# screw-front-single-a-1.net
KiCad netlist of a schematic drawn in EAGLE
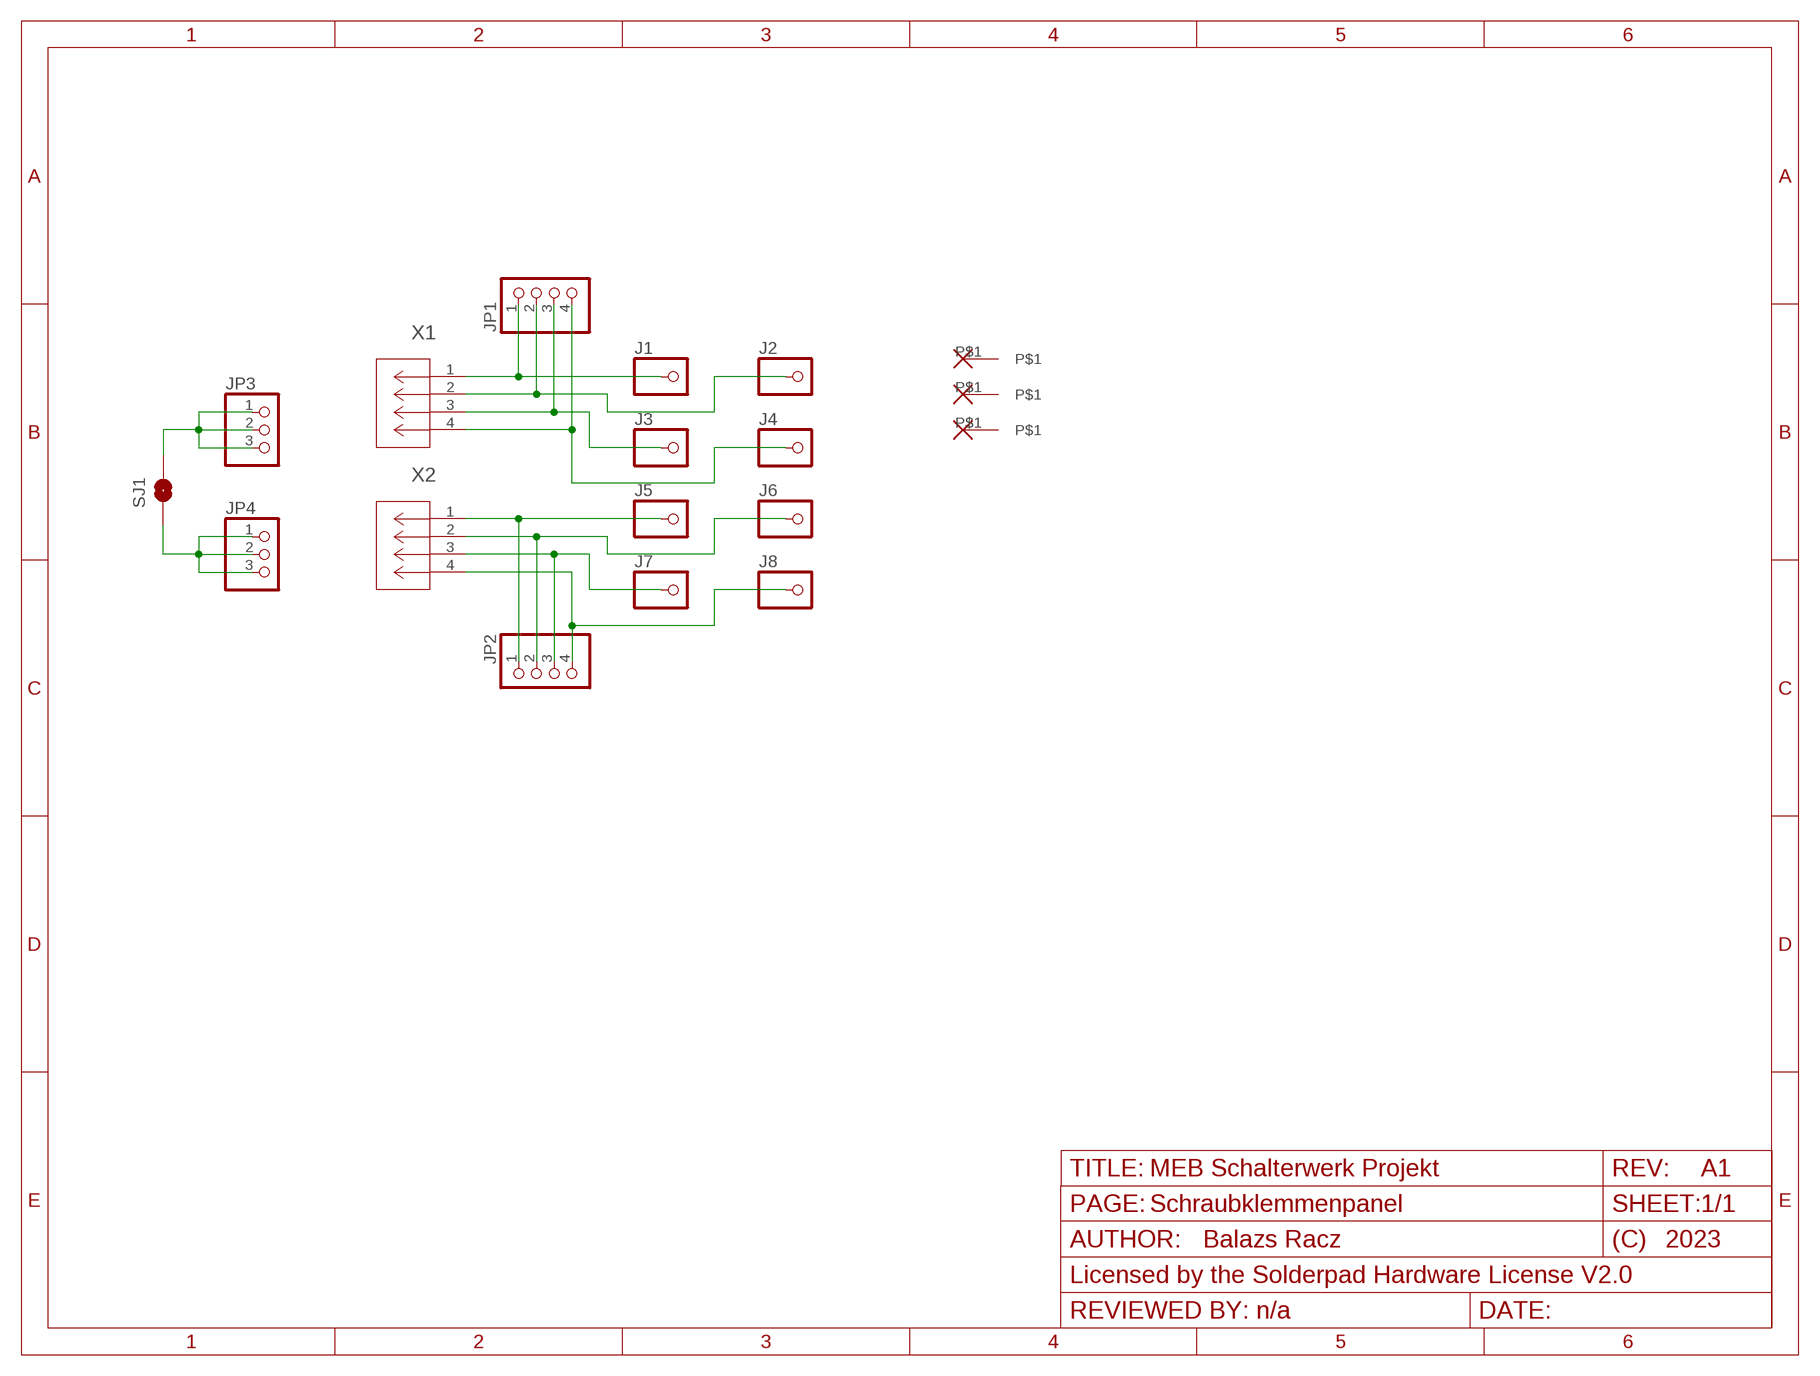
[diagram p0: schematic, sheet 1]

(export (version "E")
  (design (tool "Eeschema 10.0.6"))
  (components
    (comp (ref "H5")
      (value "ALIGN-HOLE")
      (footprint "eagle-import:ALIGNMENT-HOLE")
      (libsource (lib "eagle-import") (part "ALIGN-HOLE"))
    )
    (comp (ref "H6")
      (value "ALIGN-HOLE")
      (footprint "eagle-import:ALIGNMENT-HOLE")
      (libsource (lib "eagle-import") (part "ALIGN-HOLE"))
    )
    (comp (ref "H7")
      (value "ALIGN-HOLE")
      (footprint "eagle-import:ALIGNMENT-HOLE")
      (libsource (lib "eagle-import") (part "ALIGN-HOLE"))
    )
    (comp (ref "J1")
      (value "M4-SCREW-HOLE")
      (footprint "eagle-import:M4-SCREW-HOLE")
      (libsource (lib "eagle-import") (part "M4-SCREW-HOLE"))
    )
    (comp (ref "J2")
      (value "M4-SCREW-HOLE")
      (footprint "eagle-import:M4-SCREW-HOLE")
      (libsource (lib "eagle-import") (part "M4-SCREW-HOLE"))
    )
    (comp (ref "J3")
      (value "M4-SCREW-HOLE")
      (footprint "eagle-import:M4-SCREW-HOLE")
      (libsource (lib "eagle-import") (part "M4-SCREW-HOLE"))
    )
    (comp (ref "J4")
      (value "M4-SCREW-HOLE")
      (footprint "eagle-import:M4-SCREW-HOLE")
      (libsource (lib "eagle-import") (part "M4-SCREW-HOLE"))
    )
    (comp (ref "J5")
      (value "M4-SCREW-HOLE")
      (footprint "eagle-import:M4-SCREW-HOLE")
      (libsource (lib "eagle-import") (part "M4-SCREW-HOLE"))
    )
    (comp (ref "J6")
      (value "M4-SCREW-HOLE")
      (footprint "eagle-import:M4-SCREW-HOLE")
      (libsource (lib "eagle-import") (part "M4-SCREW-HOLE"))
    )
    (comp (ref "J7")
      (value "M4-SCREW-HOLE")
      (footprint "eagle-import:M4-SCREW-HOLE")
      (libsource (lib "eagle-import") (part "M4-SCREW-HOLE"))
    )
    (comp (ref "J8")
      (value "M4-SCREW-HOLE")
      (footprint "eagle-import:M4-SCREW-HOLE")
      (libsource (lib "eagle-import") (part "M4-SCREW-HOLE"))
    )
    (comp (ref "JP1")
      (value "PINHD-1X4")
      (footprint "eagle-import:1X04")
      (libsource (lib "eagle-import") (part "PINHD-1X4"))
    )
    (comp (ref "JP2")
      (value "PINHD-1X4")
      (footprint "eagle-import:1X04")
      (libsource (lib "eagle-import") (part "PINHD-1X4"))
    )
    (comp (ref "JP3")
      (value "PINHD-1X3")
      (footprint "eagle-import:1X03")
      (libsource (lib "eagle-import") (part "PINHD-1X3"))
    )
    (comp (ref "JP4")
      (value "PINHD-1X3")
      (footprint "eagle-import:1X03")
      (libsource (lib "eagle-import") (part "PINHD-1X3"))
    )
    (comp (ref "SJ1")
      (value "SJRND2")
      (footprint "eagle-import:SJ_RND2")
      (libsource (lib "eagle-import") (part "SJRND2"))
    )
    (comp (ref "X1")
      (value "PHNX_4P_350CONN_1984989_PXC")
      (footprint "eagle-import:PHNX_4P_350")
      (fields
        (field (name "MANUFACTURER_PART_NUMBER") "1984989")
        (field (name "COPYRIGHT") "Copyright (C) 2023 Ultra Librarian. All rights reserved.")
      )
      (libsource (lib "eagle-import") (part "PHNX_4P_350CONN_1984989_PXC"))
    )
    (comp (ref "X2")
      (value "PHNX_4P_350CONN_1984989_PXC")
      (footprint "eagle-import:PHNX_4P_350")
      (fields
        (field (name "MANUFACTURER_PART_NUMBER") "1984989")
        (field (name "COPYRIGHT") "Copyright (C) 2023 Ultra Librarian. All rights reserved.")
      )
      (libsource (lib "eagle-import") (part "PHNX_4P_350CONN_1984989_PXC"))
    )
  )
  (nets
    (net (code "1") (name "Net-(J1-1)") (class "Default")
      (node (ref "J1") (pin "P$1") (pinfunction "1_P$1") (pintype "passive"))
      (node (ref "JP1") (pin "1") (pinfunction "1_1") (pintype "passive"))
      (node (ref "X1") (pin "1") (pinfunction "1_1") (pintype "passive"))
    )
    (net (code "2") (name "Net-(J2-1)") (class "Default")
      (node (ref "J2") (pin "P$1") (pinfunction "1_P$1") (pintype "passive"))
      (node (ref "JP1") (pin "2") (pinfunction "2_2") (pintype "passive"))
      (node (ref "X1") (pin "2") (pinfunction "2_2") (pintype "passive"))
    )
    (net (code "3") (name "Net-(J3-1)") (class "Default")
      (node (ref "J3") (pin "P$1") (pinfunction "1_P$1") (pintype "passive"))
      (node (ref "JP1") (pin "3") (pinfunction "3_3") (pintype "passive"))
      (node (ref "X1") (pin "3") (pinfunction "3_3") (pintype "passive"))
    )
    (net (code "4") (name "Net-(J4-1)") (class "Default")
      (node (ref "J4") (pin "P$1") (pinfunction "1_P$1") (pintype "passive"))
      (node (ref "JP1") (pin "4") (pinfunction "4_4") (pintype "passive"))
      (node (ref "X1") (pin "4") (pinfunction "4_4") (pintype "passive"))
    )
    (net (code "5") (name "Net-(J5-1)") (class "Default")
      (node (ref "J5") (pin "P$1") (pinfunction "1_P$1") (pintype "passive"))
      (node (ref "JP2") (pin "1") (pinfunction "1_1") (pintype "passive"))
      (node (ref "X2") (pin "1") (pinfunction "1_1") (pintype "passive"))
    )
    (net (code "6") (name "Net-(J6-1)") (class "Default")
      (node (ref "J6") (pin "P$1") (pinfunction "1_P$1") (pintype "passive"))
      (node (ref "JP2") (pin "2") (pinfunction "2_2") (pintype "passive"))
      (node (ref "X2") (pin "2") (pinfunction "2_2") (pintype "passive"))
    )
    (net (code "7") (name "Net-(J7-1)") (class "Default")
      (node (ref "J7") (pin "P$1") (pinfunction "1_P$1") (pintype "passive"))
      (node (ref "JP2") (pin "3") (pinfunction "3_3") (pintype "passive"))
      (node (ref "X2") (pin "3") (pinfunction "3_3") (pintype "passive"))
    )
    (net (code "8") (name "Net-(J8-1)") (class "Default")
      (node (ref "J8") (pin "P$1") (pinfunction "1_P$1") (pintype "passive"))
      (node (ref "JP2") (pin "4") (pinfunction "4_4") (pintype "passive"))
      (node (ref "X2") (pin "4") (pinfunction "4_4") (pintype "passive"))
    )
    (net (code "9") (name "Net-(SJ1-1)") (class "Default")
      (node (ref "JP4") (pin "1") (pinfunction "1_1") (pintype "passive"))
      (node (ref "JP4") (pin "2") (pinfunction "2_2") (pintype "passive"))
      (node (ref "JP4") (pin "3") (pinfunction "3_3") (pintype "passive"))
      (node (ref "SJ1") (pin "P$1") (pinfunction "1_P$1") (pintype "passive"))
    )
    (net (code "10") (name "Net-(SJ1-2)") (class "Default")
      (node (ref "JP3") (pin "1") (pinfunction "1_1") (pintype "passive"))
      (node (ref "JP3") (pin "2") (pinfunction "2_2") (pintype "passive"))
      (node (ref "JP3") (pin "3") (pinfunction "3_3") (pintype "passive"))
      (node (ref "SJ1") (pin "P$2") (pinfunction "2_P$2") (pintype "passive"))
    )
    (net (code "11") (name "unconnected-(H5-PadP$1)") (class "Default")
      (node (ref "H5") (pin "P$1") (pinfunction "P$1_P$1") (pintype "bidirectional"))
    )
    (net (code "12") (name "unconnected-(H6-PadP$1)") (class "Default")
      (node (ref "H6") (pin "P$1") (pinfunction "P$1_P$1") (pintype "bidirectional"))
    )
    (net (code "13") (name "unconnected-(H7-PadP$1)") (class "Default")
      (node (ref "H7") (pin "P$1") (pinfunction "P$1_P$1") (pintype "bidirectional"))
    )
  )
)
